# BluetoothAdapter_v2.net
KiCad netlist of a schematic drawn in EAGLE
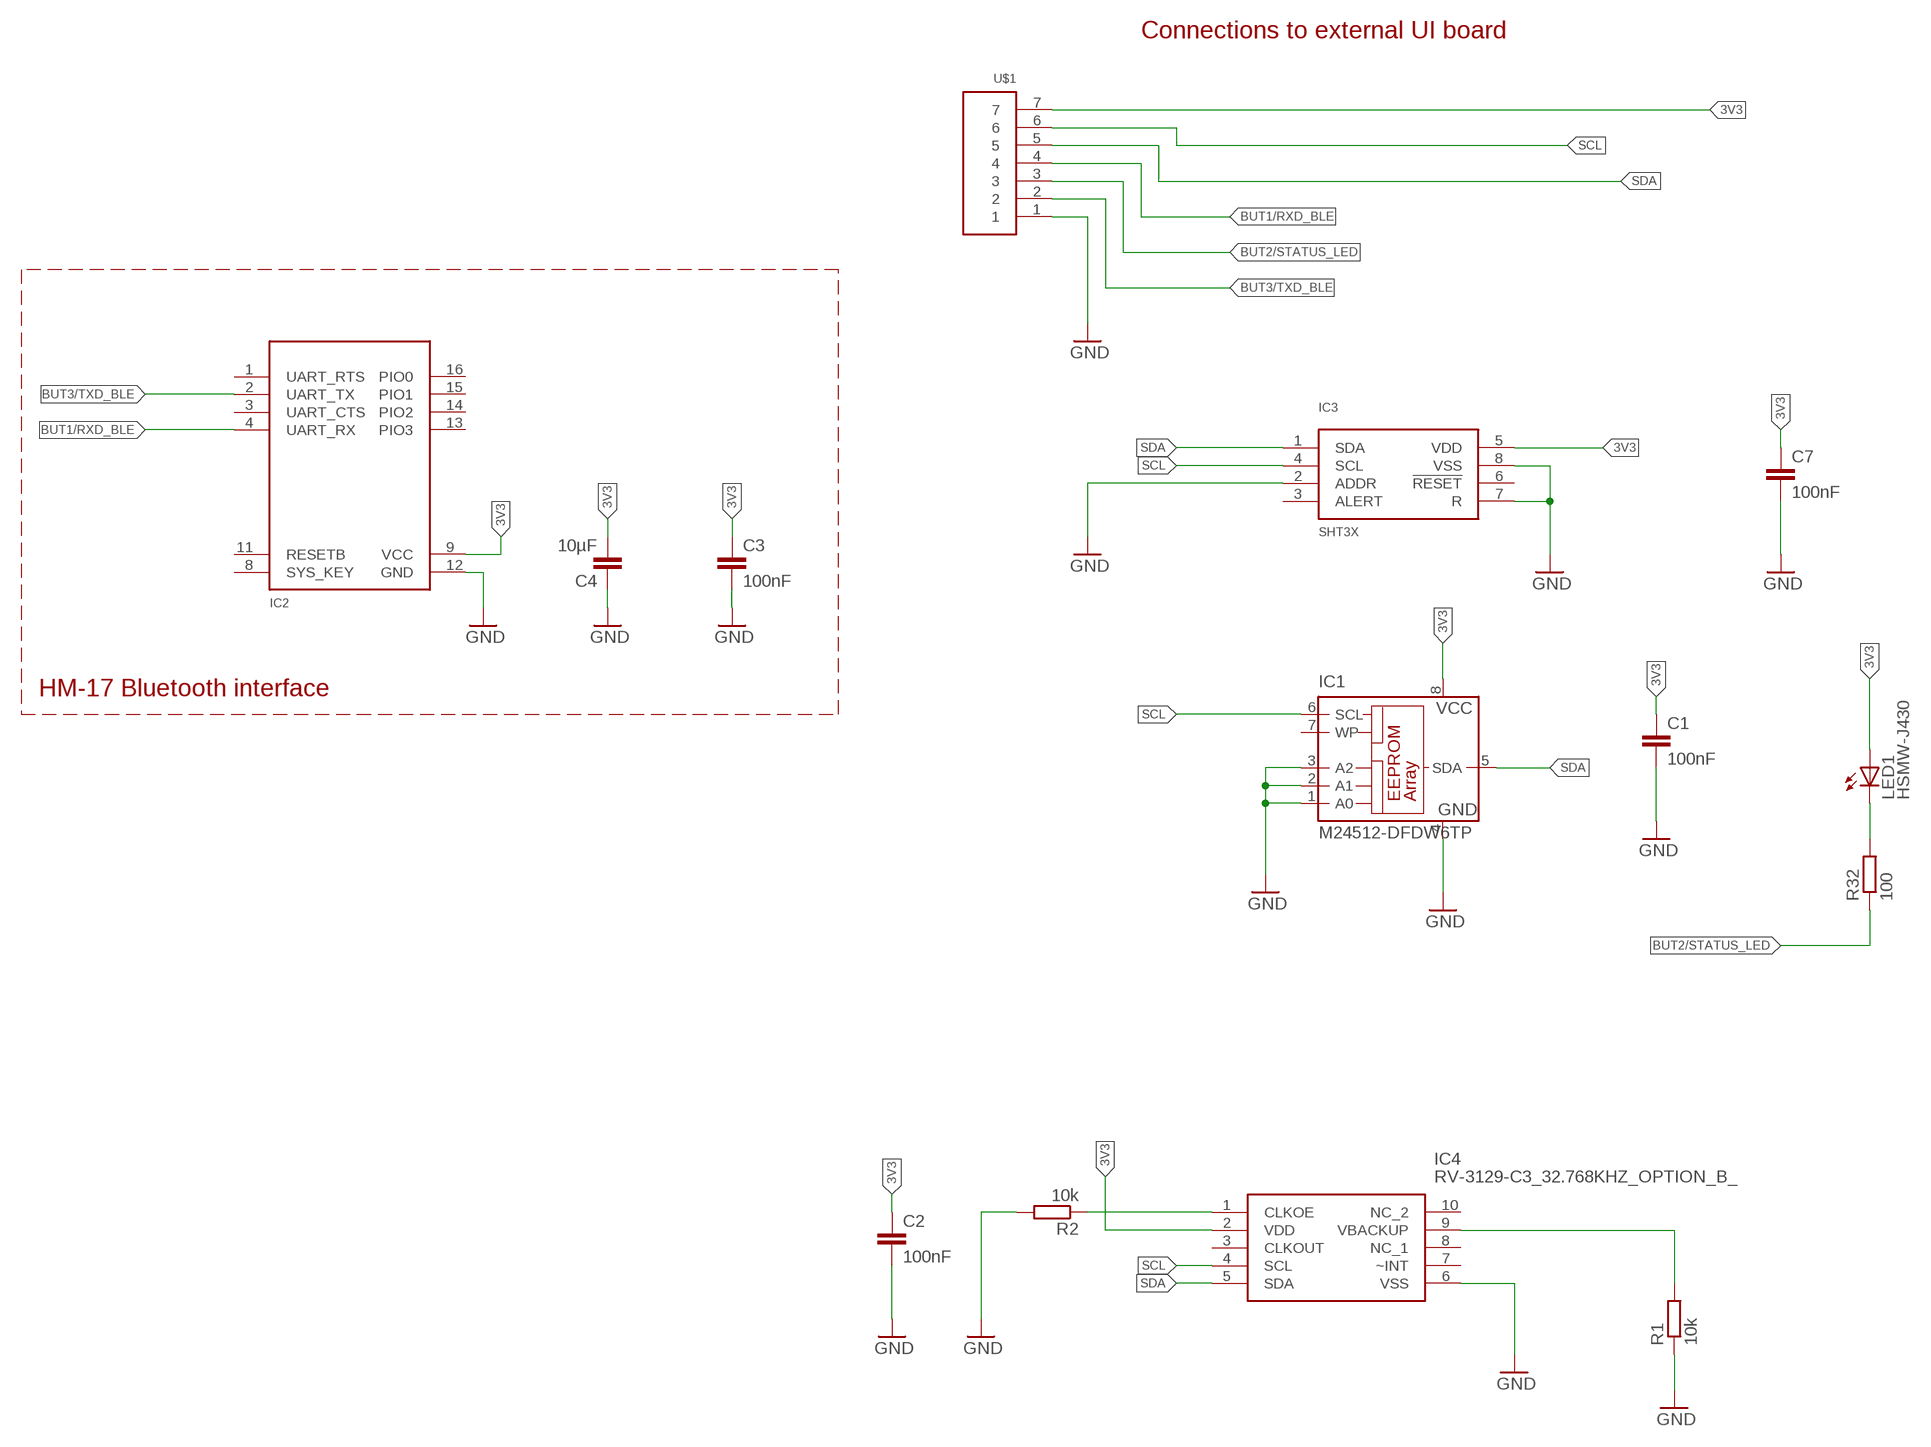
[diagram p0: schematic, sheet 1]

(export (version "E")
  (design (tool "Eeschema 10.0.6"))
  (components
    (comp (ref "C1")
      (value "100nF")
      (footprint "eagle-import:C0402")
      (libsource (lib "eagle-import") (part "C-EUC0402"))
    )
    (comp (ref "C2")
      (value "100nF")
      (footprint "eagle-import:C0402")
      (libsource (lib "eagle-import") (part "C-EUC0402"))
    )
    (comp (ref "C3")
      (value "100nF")
      (footprint "eagle-import:C0402")
      (libsource (lib "eagle-import") (part "C-EUC0402"))
    )
    (comp (ref "C4")
      (value "10µF")
      (footprint "eagle-import:C0805K")
      (libsource (lib "eagle-import") (part "C-EUC0805K"))
    )
    (comp (ref "C7")
      (value "100nF")
      (footprint "eagle-import:C0402")
      (libsource (lib "eagle-import") (part "C-EUC0402"))
    )
    (comp (ref "IC1")
      (value "M24512-DFDW6TP")
      (footprint "eagle-import:TSSOP8")
      (fields (field (name "MF") "MICROCHIP") (field (name "MPN") "24LC128-I/ST"))
      (libsource (lib "eagle-import") (part "24STLC128"))
    )
    (comp (ref "IC2")
      (value "HM17")
      (footprint "eagle-import:HM17")
      (libsource (lib "eagle-import") (part "HM17"))
    )
    (comp (ref "IC3")
      (value "SHT3X")
      (footprint "eagle-import:TDFN8-2.5X2.5MM")
      (libsource (lib "eagle-import") (part "SHT3X"))
    )
    (comp (ref "IC4")
      (value "RV-3129-C3_32.768KHZ_OPTION_B_")
      (footprint "eagle-import:RV3129C3")
      (fields
        (field (name "MANUFACTURER_PART_NUMBER") "RV-3129-C3 32.768kHz OPTION B TA QC")
        (field (name "MOUSER_PART_NUMBER") "428-203634-MG01")
      )
      (libsource (lib "eagle-import") (part "RV-3129-C3_32.768KHZ_OPTION_B_"))
    )
    (comp (ref "LED1")
      (value "HSMW-J430")
      (footprint "eagle-import:1206")
      (libsource (lib "eagle-import") (part "LEDSMT1206"))
    )
    (comp (ref "R1")
      (value "10k")
      (footprint "eagle-import:R0603")
      (libsource (lib "eagle-import") (part "R-EU_R0603"))
    )
    (comp (ref "R2")
      (value "10k")
      (footprint "eagle-import:R0603")
      (libsource (lib "eagle-import") (part "R-EU_R0603"))
    )
    (comp (ref "R32")
      (value "100")
      (footprint "eagle-import:R0603")
      (libsource (lib "eagle-import") (part "R-EU_R0603"))
    )
    (comp (ref "U$1")
      (value "WIREPAD1X7")
      (footprint "eagle-import:WIREPAD1X7")
      (libsource (lib "eagle-import") (part "WIREPAD1X7"))
    )
  )
  (nets
    (net (code "1") (name "3V3") (class "Default")
      (node (ref "C1") (pin "1") (pinfunction "1_1") (pintype "passive"))
      (node (ref "C2") (pin "1") (pinfunction "1_1") (pintype "passive"))
      (node (ref "C3") (pin "1") (pinfunction "1_1") (pintype "passive"))
      (node (ref "C4") (pin "2") (pinfunction "2_2") (pintype "passive"))
      (node (ref "C7") (pin "1") (pinfunction "1_1") (pintype "passive"))
      (node (ref "IC1") (pin "8") (pinfunction "VCC_8") (pintype "power_in"))
      (node (ref "IC2") (pin "9") (pinfunction "VCC_9") (pintype "power_in"))
      (node (ref "IC3") (pin "5") (pinfunction "VDD_5") (pintype "bidirectional"))
      (node (ref "IC4") (pin "2") (pinfunction "VDD_2") (pintype "bidirectional"))
      (node (ref "LED1") (pin "A") (pinfunction "A_A") (pintype "passive"))
      (node (ref "U$1") (pin "7") (pinfunction "7_7") (pintype "bidirectional"))
    )
    (net (code "2") (name "BUT1{slash}RXD_BLE") (class "Default")
      (node (ref "IC2") (pin "4") (pinfunction "UART_RX_4") (pintype "bidirectional"))
      (node (ref "U$1") (pin "4") (pinfunction "4_4") (pintype "bidirectional"))
    )
    (net (code "3") (name "BUT2{slash}STATUS_LED") (class "Default")
      (node (ref "R32") (pin "1") (pinfunction "1_1") (pintype "passive"))
      (node (ref "U$1") (pin "3") (pinfunction "3_3") (pintype "bidirectional"))
    )
    (net (code "4") (name "BUT3{slash}TXD_BLE") (class "Default")
      (node (ref "IC2") (pin "2") (pinfunction "UART_TX_2") (pintype "bidirectional"))
      (node (ref "U$1") (pin "2") (pinfunction "2_2") (pintype "bidirectional"))
    )
    (net (code "5") (name "GND") (class "Default")
      (node (ref "C1") (pin "2") (pinfunction "2_2") (pintype "passive"))
      (node (ref "C2") (pin "2") (pinfunction "2_2") (pintype "passive"))
      (node (ref "C3") (pin "2") (pinfunction "2_2") (pintype "passive"))
      (node (ref "C4") (pin "1") (pinfunction "1_1") (pintype "passive"))
      (node (ref "C7") (pin "2") (pinfunction "2_2") (pintype "passive"))
      (node (ref "IC1") (pin "1") (pinfunction "A0_1") (pintype "input"))
      (node (ref "IC1") (pin "2") (pinfunction "A1_2") (pintype "input"))
      (node (ref "IC1") (pin "3") (pinfunction "A2_3") (pintype "input"))
      (node (ref "IC1") (pin "4") (pinfunction "GND_4") (pintype "power_in"))
      (node (ref "IC2") (pin "12") (pinfunction "GND_12") (pintype "power_in"))
      (node (ref "IC3") (pin "2") (pinfunction "ADDR_2") (pintype "bidirectional"))
      (node (ref "IC3") (pin "7") (pinfunction "R_7") (pintype "bidirectional"))
      (node (ref "IC3") (pin "8") (pinfunction "VSS_8") (pintype "bidirectional"))
      (node (ref "IC4") (pin "6") (pinfunction "VSS_6") (pintype "bidirectional"))
      (node (ref "R1") (pin "1") (pinfunction "1_1") (pintype "passive"))
      (node (ref "R2") (pin "2") (pinfunction "2_2") (pintype "passive"))
      (node (ref "U$1") (pin "1") (pinfunction "1_1") (pintype "bidirectional"))
    )
    (net (code "6") (name "Net-(IC4-CLKOE)") (class "Default")
      (node (ref "IC4") (pin "1") (pinfunction "CLKOE_1") (pintype "bidirectional"))
      (node (ref "R2") (pin "1") (pinfunction "1_1") (pintype "passive"))
    )
    (net (code "7") (name "Net-(IC4-VBACKUP)") (class "Default")
      (node (ref "IC4") (pin "9") (pinfunction "VBACKUP_9") (pintype "bidirectional"))
      (node (ref "R1") (pin "2") (pinfunction "2_2") (pintype "passive"))
    )
    (net (code "8") (name "Net-(LED1-PadC)") (class "Default")
      (node (ref "LED1") (pin "C") (pinfunction "C_C") (pintype "passive"))
      (node (ref "R32") (pin "2") (pinfunction "2_2") (pintype "passive"))
    )
    (net (code "9") (name "SCL") (class "Default")
      (node (ref "IC1") (pin "6") (pinfunction "SCL_6") (pintype "input"))
      (node (ref "IC3") (pin "4") (pinfunction "SCL_4") (pintype "bidirectional"))
      (node (ref "IC4") (pin "4") (pinfunction "SCL_4") (pintype "bidirectional"))
      (node (ref "U$1") (pin "6") (pinfunction "6_6") (pintype "bidirectional"))
    )
    (net (code "10") (name "SDA") (class "Default")
      (node (ref "IC1") (pin "5") (pinfunction "SDA_5") (pintype "bidirectional"))
      (node (ref "IC3") (pin "1") (pinfunction "SDA_1") (pintype "bidirectional"))
      (node (ref "IC4") (pin "5") (pinfunction "SDA_5") (pintype "bidirectional"))
      (node (ref "U$1") (pin "5") (pinfunction "5_5") (pintype "bidirectional"))
    )
    (net (code "11") (name "unconnected-(IC1-WP-Pad7)") (class "Default")
      (node (ref "IC1") (pin "7") (pinfunction "WP_7") (pintype "input"))
    )
    (net (code "12") (name "unconnected-(IC2-PIO0-Pad16)") (class "Default")
      (node (ref "IC2") (pin "16") (pinfunction "PIO0_16") (pintype "bidirectional"))
    )
    (net (code "13") (name "unconnected-(IC2-PIO1-Pad15)") (class "Default")
      (node (ref "IC2") (pin "15") (pinfunction "PIO1_15") (pintype "bidirectional"))
    )
    (net (code "14") (name "unconnected-(IC2-PIO2-Pad14)") (class "Default")
      (node (ref "IC2") (pin "14") (pinfunction "PIO2_14") (pintype "bidirectional"))
    )
    (net (code "15") (name "unconnected-(IC2-PIO3-Pad13)") (class "Default")
      (node (ref "IC2") (pin "13") (pinfunction "PIO3_13") (pintype "bidirectional"))
    )
    (net (code "16") (name "unconnected-(IC2-RESETB-Pad11)") (class "Default")
      (node (ref "IC2") (pin "11") (pinfunction "RESETB_11") (pintype "bidirectional"))
    )
    (net (code "17") (name "unconnected-(IC2-SYS_KEY-Pad8)") (class "Default")
      (node (ref "IC2") (pin "8") (pinfunction "SYS_KEY_8") (pintype "bidirectional"))
    )
    (net (code "18") (name "unconnected-(IC2-UART_CTS-Pad3)") (class "Default")
      (node (ref "IC2") (pin "3") (pinfunction "UART_CTS_3") (pintype "bidirectional"))
    )
    (net (code "19") (name "unconnected-(IC2-UART_RTS-Pad1)") (class "Default")
      (node (ref "IC2") (pin "1") (pinfunction "UART_RTS_1") (pintype "bidirectional"))
    )
    (net (code "20") (name "unconnected-(IC3-ALERT-Pad3)") (class "Default")
      (node (ref "IC3") (pin "3") (pinfunction "ALERT_3") (pintype "bidirectional"))
    )
    (net (code "21") (name "unconnected-(IC3-~{RESET}-Pad6)") (class "Default")
      (node (ref "IC3") (pin "6") (pinfunction "~{RESET}_6") (pintype "bidirectional"))
    )
    (net (code "22") (name "unconnected-(IC4-CLKOUT-Pad3)") (class "Default")
      (node (ref "IC4") (pin "3") (pinfunction "CLKOUT_3") (pintype "bidirectional"))
    )
    (net (code "23") (name "unconnected-(IC4-NC_1-Pad8)") (class "Default")
      (node (ref "IC4") (pin "8") (pinfunction "NC_1_8") (pintype "bidirectional"))
    )
    (net (code "24") (name "unconnected-(IC4-NC_2-Pad10)") (class "Default")
      (node (ref "IC4") (pin "10") (pinfunction "NC_2_10") (pintype "bidirectional"))
    )
    (net (code "25") (name "unconnected-(IC4-~{INT}-Pad7)") (class "Default")
      (node (ref "IC4") (pin "7") (pinfunction "~{INT}_7") (pintype "bidirectional"))
    )
  )
)
